# BMS-MCU.net
KiCad netlist of a schematic drawn in Altium Designer
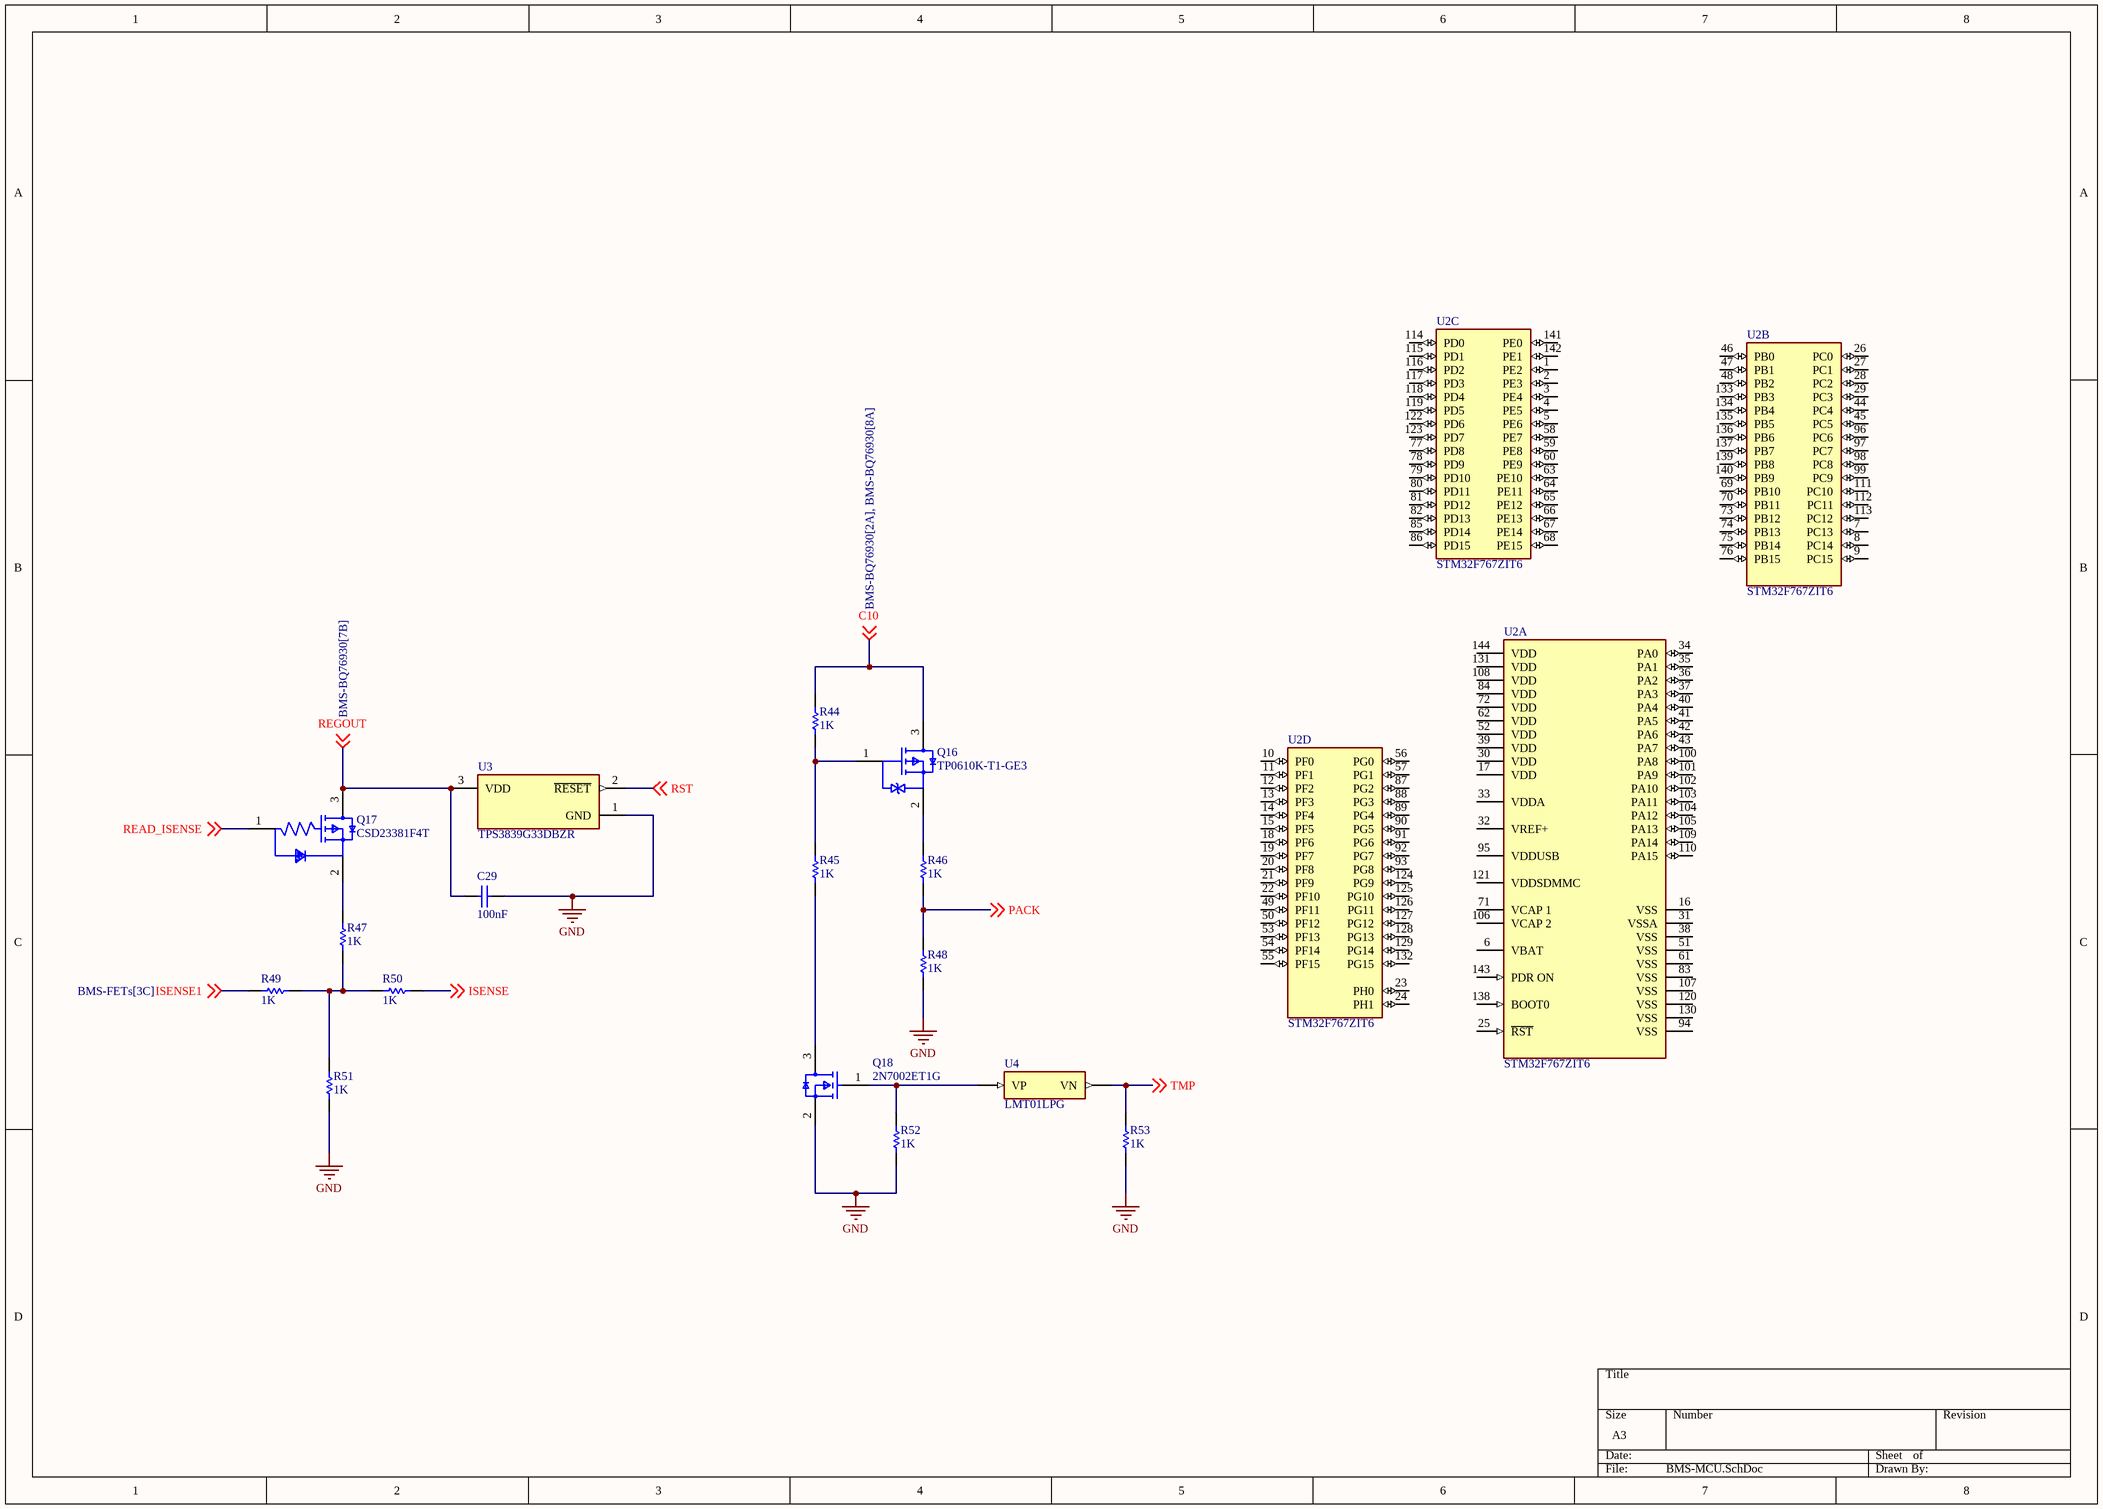
[diagram p0: BMS-MCU.SchDoc]

(export (version "E")
  (design (tool "Eeschema 10.0.6"))
  (components
    (comp (ref "C29")
      (value "885012206046")
      (footprint "WCAP-CSGP_0603_L1.6W0.8H0.8_Reflow")
      (fields (field (name "TOLERANCE") "10%") (field (name "CAPACITANCE") "100nF"))
      (libsource (lib "BMS-lib") (part "CMP-03913-53914755-1"))
    )
    (comp (ref "Q16")
      (value "TP0610K-T1-GE3")
      (footprint "FP-S-03946-IPC_C")
      (description "MOSFET P-CH 60V 185MA SOT23-3")
      (libsource (lib "BMS-lib") (part "CMP-02550-000326-1"))
    )
    (comp (ref "Q17")
      (value "CSD23381F4T")
      (footprint "FP-YJC0003A-MFG")
      (description "MOSFET P-CH 12V 2.3A 3PICOSTAR")
      (libsource (lib "BMS-lib") (part "CMP-04962-000081-1"))
    )
    (comp (ref "Q18")
      (value "2N7002ET1G")
      (footprint "FP-318-08-MFG")
      (description "MOSFET N-CH 60V 260MA SOT-23")
      (libsource (lib "BMS-lib") (part "CMP-1058-00769-2"))
    )
    (comp (ref "R44")
      (value "1K")
      (description "Resistor")
      (libsource (lib "Simulation Generic Components") (part "Resistor"))
    )
    (comp (ref "R45")
      (value "1K")
      (description "Resistor")
      (libsource (lib "Simulation Generic Components") (part "Resistor"))
    )
    (comp (ref "R46")
      (value "1K")
      (description "Resistor")
      (libsource (lib "Simulation Generic Components") (part "Resistor"))
    )
    (comp (ref "R47")
      (value "1K")
      (description "Resistor")
      (libsource (lib "Simulation Generic Components") (part "Resistor"))
    )
    (comp (ref "R48")
      (value "1K")
      (description "Resistor")
      (libsource (lib "Simulation Generic Components") (part "Resistor"))
    )
    (comp (ref "R49")
      (value "1K")
      (description "Resistor")
      (libsource (lib "Simulation Generic Components") (part "Resistor"))
    )
    (comp (ref "R50")
      (value "1K")
      (description "Resistor")
      (libsource (lib "Simulation Generic Components") (part "Resistor"))
    )
    (comp (ref "R51")
      (value "1K")
      (description "Resistor")
      (libsource (lib "Simulation Generic Components") (part "Resistor"))
    )
    (comp (ref "R52")
      (value "1K")
      (description "Resistor")
      (libsource (lib "Simulation Generic Components") (part "Resistor"))
    )
    (comp (ref "R53")
      (value "1K")
      (description "Resistor")
      (libsource (lib "Simulation Generic Components") (part "Resistor"))
    )
    (comp (ref "U2")
      (value "STM32F767ZIT6")
      (footprint "FP-LQFP144-1A-IPC_B")
      (description "IC MCU 32BIT 2MB FLASH 144LQFP")
      (fields
        (field (name "OCTOPART") "https://octopart.com/stm32f767zit6-stmicroelectronics-70527068")
        (field (name "MANUFACTURER") "STMicroelectronics")
      )
      (libsource (lib "BMS-lib") (part "CMP-12105-000074-1"))
    )
    (comp (ref "U3")
      (value "TPS3839G33DBZR")
      (footprint "FP-DBZ0003A-MFG")
      (description "IC SUPERVISOR 1 CHANNEL SOT23-3")
      (libsource (lib "BMS-lib") (part "CMP-04919-000025-1"))
    )
    (comp (ref "U4")
      (value "LMT01LPG")
      (footprint "FP-LPG0002A-MFG")
      (description "SENSOR DIGITAL -50C-150C TO92-2")
      (fields
        (field (name "OCTOPART") "https://octopart.com/lmt01lpg-texas+instruments-60770464")
        (field (name "MANUFACTURER") "Texas Instruments")
      )
      (libsource (lib "BMS-lib") (part "CMP-04948-000023-1"))
    )
  )
  (nets
    (net (code "1") (name "C10") (class "Default")
      (node (ref "Q16") (pin "3") (pinfunction "D_3") (pintype "passive"))
      (node (ref "R44") (pin "2") (pinfunction "2_2") (pintype "passive"))
    )
    (net (code "2") (name "GND") (class "Default")
      (node (ref "C29") (pin "2") (pinfunction "2_2") (pintype "passive"))
      (node (ref "Q18") (pin "2") (pinfunction "Source_2") (pintype "passive"))
      (node (ref "R48") (pin "1") (pinfunction "1_1") (pintype "passive"))
      (node (ref "R51") (pin "1") (pinfunction "1_1") (pintype "passive"))
      (node (ref "R52") (pin "1") (pinfunction "1_1") (pintype "passive"))
      (node (ref "R53") (pin "1") (pinfunction "1_1") (pintype "passive"))
      (node (ref "U3") (pin "1") (pinfunction "GND_1") (pintype "power_in"))
    )
    (net (code "3") (name "ISENSE") (class "Default")
      (node (ref "R50") (pin "1") (pinfunction "1_1") (pintype "passive"))
    )
    (net (code "4") (name "ISENSE1") (class "Default")
      (node (ref "R49") (pin "2") (pinfunction "2_2") (pintype "passive"))
    )
    (net (code "5") (name "Net-(Q16-G)") (class "Default")
      (node (ref "Q16") (pin "1") (pinfunction "G_1") (pintype "passive"))
      (node (ref "R44") (pin "1") (pinfunction "1_1") (pintype "passive"))
      (node (ref "R45") (pin "2") (pinfunction "2_2") (pintype "passive"))
    )
    (net (code "6") (name "Net-(Q16-S)") (class "Default")
      (node (ref "Q16") (pin "2") (pinfunction "S_2") (pintype "passive"))
      (node (ref "R46") (pin "2") (pinfunction "2_2") (pintype "passive"))
    )
    (net (code "7") (name "Net-(Q17-S)") (class "Default")
      (node (ref "Q17") (pin "2") (pinfunction "S_2") (pintype "passive"))
      (node (ref "R47") (pin "2") (pinfunction "2_2") (pintype "passive"))
    )
    (net (code "8") (name "Net-(Q18-Drain)") (class "Default")
      (node (ref "Q18") (pin "3") (pinfunction "Drain_3") (pintype "passive"))
      (node (ref "R45") (pin "1") (pinfunction "1_1") (pintype "passive"))
    )
    (net (code "9") (name "Net-(Q18-Gate)") (class "Default")
      (node (ref "Q18") (pin "1") (pinfunction "Gate_1") (pintype "passive"))
      (node (ref "R52") (pin "2") (pinfunction "2_2") (pintype "passive"))
      (node (ref "U4") (pin "2") (pinfunction "VP_2") (pintype "input"))
    )
    (net (code "10") (name "Net-(R47-Pad1)") (class "Default")
      (node (ref "R47") (pin "1") (pinfunction "1_1") (pintype "passive"))
      (node (ref "R49") (pin "1") (pinfunction "1_1") (pintype "passive"))
      (node (ref "R50") (pin "2") (pinfunction "2_2") (pintype "passive"))
      (node (ref "R51") (pin "2") (pinfunction "2_2") (pintype "passive"))
    )
    (net (code "11") (name "PACK") (class "Default")
      (node (ref "R46") (pin "1") (pinfunction "1_1") (pintype "passive"))
      (node (ref "R48") (pin "2") (pinfunction "2_2") (pintype "passive"))
    )
    (net (code "12") (name "READ_ISENSE") (class "Default")
      (node (ref "Q17") (pin "1") (pinfunction "G_1") (pintype "passive"))
    )
    (net (code "13") (name "REGOUT") (class "Default")
      (node (ref "C29") (pin "1") (pinfunction "1_1") (pintype "passive"))
      (node (ref "Q17") (pin "3") (pinfunction "D_3") (pintype "passive"))
      (node (ref "U3") (pin "3") (pinfunction "VDD_3") (pintype "power_in"))
    )
    (net (code "14") (name "RST") (class "Default")
      (node (ref "U3") (pin "2") (pinfunction "~{RESET}_2") (pintype "output"))
    )
    (net (code "15") (name "TMP") (class "Default")
      (node (ref "R53") (pin "2") (pinfunction "2_2") (pintype "passive"))
      (node (ref "U4") (pin "1") (pinfunction "VN_1") (pintype "output"))
    )
    (net (code "16") (name "unconnected-(U2A-BOOT0-Pad138)") (class "Default")
      (node (ref "U2") (pin "138") (pinfunction "BOOT0_138") (pintype "input"))
    )
    (net (code "17") (name "unconnected-(U2A-PA0-Pad34)") (class "Default")
      (node (ref "U2") (pin "34") (pinfunction "PA0_34") (pintype "bidirectional"))
    )
    (net (code "18") (name "unconnected-(U2A-PA1-Pad35)") (class "Default")
      (node (ref "U2") (pin "35") (pinfunction "PA1_35") (pintype "bidirectional"))
    )
    (net (code "19") (name "unconnected-(U2A-PA2-Pad36)") (class "Default")
      (node (ref "U2") (pin "36") (pinfunction "PA2_36") (pintype "bidirectional"))
    )
    (net (code "20") (name "unconnected-(U2A-PA3-Pad37)") (class "Default")
      (node (ref "U2") (pin "37") (pinfunction "PA3_37") (pintype "bidirectional"))
    )
    (net (code "21") (name "unconnected-(U2A-PA4-Pad40)") (class "Default")
      (node (ref "U2") (pin "40") (pinfunction "PA4_40") (pintype "bidirectional"))
    )
    (net (code "22") (name "unconnected-(U2A-PA5-Pad41)") (class "Default")
      (node (ref "U2") (pin "41") (pinfunction "PA5_41") (pintype "bidirectional"))
    )
    (net (code "23") (name "unconnected-(U2A-PA6-Pad42)") (class "Default")
      (node (ref "U2") (pin "42") (pinfunction "PA6_42") (pintype "bidirectional"))
    )
    (net (code "24") (name "unconnected-(U2A-PA7-Pad43)") (class "Default")
      (node (ref "U2") (pin "43") (pinfunction "PA7_43") (pintype "bidirectional"))
    )
    (net (code "25") (name "unconnected-(U2A-PA8-Pad100)") (class "Default")
      (node (ref "U2") (pin "100") (pinfunction "PA8_100") (pintype "bidirectional"))
    )
    (net (code "26") (name "unconnected-(U2A-PA9-Pad101)") (class "Default")
      (node (ref "U2") (pin "101") (pinfunction "PA9_101") (pintype "bidirectional"))
    )
    (net (code "27") (name "unconnected-(U2A-PA10-Pad102)") (class "Default")
      (node (ref "U2") (pin "102") (pinfunction "PA10_102") (pintype "bidirectional"))
    )
    (net (code "28") (name "unconnected-(U2A-PA11-Pad103)") (class "Default")
      (node (ref "U2") (pin "103") (pinfunction "PA11_103") (pintype "bidirectional"))
    )
    (net (code "29") (name "unconnected-(U2A-PA12-Pad104)") (class "Default")
      (node (ref "U2") (pin "104") (pinfunction "PA12_104") (pintype "bidirectional"))
    )
    (net (code "30") (name "unconnected-(U2A-PA13-Pad105)") (class "Default")
      (node (ref "U2") (pin "105") (pinfunction "PA13_105") (pintype "bidirectional"))
    )
    (net (code "31") (name "unconnected-(U2A-PA14-Pad109)") (class "Default")
      (node (ref "U2") (pin "109") (pinfunction "PA14_109") (pintype "bidirectional"))
    )
    (net (code "32") (name "unconnected-(U2A-PA15-Pad110)") (class "Default")
      (node (ref "U2") (pin "110") (pinfunction "PA15_110") (pintype "bidirectional"))
    )
    (net (code "33") (name "unconnected-(U2A-PDR_ON-Pad143)") (class "Default")
      (node (ref "U2") (pin "143") (pinfunction "PDR_ON_143") (pintype "input"))
    )
    (net (code "34") (name "unconnected-(U2A-VBAT-Pad6)") (class "Default")
      (node (ref "U2") (pin "6") (pinfunction "VBAT_6") (pintype "power_in"))
    )
    (net (code "35") (name "unconnected-(U2A-VCAP_1-Pad71)") (class "Default")
      (node (ref "U2") (pin "71") (pinfunction "VCAP_1_71") (pintype "power_in"))
    )
    (net (code "36") (name "unconnected-(U2A-VCAP_2-Pad106)") (class "Default")
      (node (ref "U2") (pin "106") (pinfunction "VCAP_2_106") (pintype "power_in"))
    )
    (net (code "37") (name "unconnected-(U2A-VDD-Pad17)") (class "Default")
      (node (ref "U2") (pin "17") (pinfunction "VDD_17") (pintype "power_in"))
    )
    (net (code "38") (name "unconnected-(U2A-VDD-Pad30)") (class "Default")
      (node (ref "U2") (pin "30") (pinfunction "VDD_30") (pintype "power_in"))
    )
    (net (code "39") (name "unconnected-(U2A-VDD-Pad39)") (class "Default")
      (node (ref "U2") (pin "39") (pinfunction "VDD_39") (pintype "power_in"))
    )
    (net (code "40") (name "unconnected-(U2A-VDD-Pad52)") (class "Default")
      (node (ref "U2") (pin "52") (pinfunction "VDD_52") (pintype "power_in"))
    )
    (net (code "41") (name "unconnected-(U2A-VDD-Pad62)") (class "Default")
      (node (ref "U2") (pin "62") (pinfunction "VDD_62") (pintype "power_in"))
    )
    (net (code "42") (name "unconnected-(U2A-VDD-Pad72)") (class "Default")
      (node (ref "U2") (pin "72") (pinfunction "VDD_72") (pintype "power_in"))
    )
    (net (code "43") (name "unconnected-(U2A-VDD-Pad84)") (class "Default")
      (node (ref "U2") (pin "84") (pinfunction "VDD_84") (pintype "power_in"))
    )
    (net (code "44") (name "unconnected-(U2A-VDD-Pad108)") (class "Default")
      (node (ref "U2") (pin "108") (pinfunction "VDD_108") (pintype "power_in"))
    )
    (net (code "45") (name "unconnected-(U2A-VDD-Pad131)") (class "Default")
      (node (ref "U2") (pin "131") (pinfunction "VDD_131") (pintype "power_in"))
    )
    (net (code "46") (name "unconnected-(U2A-VDD-Pad144)") (class "Default")
      (node (ref "U2") (pin "144") (pinfunction "VDD_144") (pintype "power_in"))
    )
    (net (code "47") (name "unconnected-(U2A-VDDA-Pad33)") (class "Default")
      (node (ref "U2") (pin "33") (pinfunction "VDDA_33") (pintype "power_in"))
    )
    (net (code "48") (name "unconnected-(U2A-VDDSDMMC-Pad121)") (class "Default")
      (node (ref "U2") (pin "121") (pinfunction "VDDSDMMC_121") (pintype "power_in"))
    )
    (net (code "49") (name "unconnected-(U2A-VDDUSB-Pad95)") (class "Default")
      (node (ref "U2") (pin "95") (pinfunction "VDDUSB_95") (pintype "power_in"))
    )
    (net (code "50") (name "unconnected-(U2A-VREF+-Pad32)") (class "Default")
      (node (ref "U2") (pin "32") (pinfunction "VREF+_32") (pintype "power_in"))
    )
    (net (code "51") (name "unconnected-(U2A-VSS-Pad16)") (class "Default")
      (node (ref "U2") (pin "16") (pinfunction "VSS_16") (pintype "power_in"))
    )
    (net (code "52") (name "unconnected-(U2A-VSS-Pad38)") (class "Default")
      (node (ref "U2") (pin "38") (pinfunction "VSS_38") (pintype "power_in"))
    )
    (net (code "53") (name "unconnected-(U2A-VSS-Pad51)") (class "Default")
      (node (ref "U2") (pin "51") (pinfunction "VSS_51") (pintype "power_in"))
    )
    (net (code "54") (name "unconnected-(U2A-VSS-Pad61)") (class "Default")
      (node (ref "U2") (pin "61") (pinfunction "VSS_61") (pintype "power_in"))
    )
    (net (code "55") (name "unconnected-(U2A-VSS-Pad83)") (class "Default")
      (node (ref "U2") (pin "83") (pinfunction "VSS_83") (pintype "power_in"))
    )
    (net (code "56") (name "unconnected-(U2A-VSS-Pad94)") (class "Default")
      (node (ref "U2") (pin "94") (pinfunction "VSS_94") (pintype "power_in"))
    )
    (net (code "57") (name "unconnected-(U2A-VSS-Pad107)") (class "Default")
      (node (ref "U2") (pin "107") (pinfunction "VSS_107") (pintype "power_in"))
    )
    (net (code "58") (name "unconnected-(U2A-VSS-Pad120)") (class "Default")
      (node (ref "U2") (pin "120") (pinfunction "VSS_120") (pintype "power_in"))
    )
    (net (code "59") (name "unconnected-(U2A-VSS-Pad130)") (class "Default")
      (node (ref "U2") (pin "130") (pinfunction "VSS_130") (pintype "power_in"))
    )
    (net (code "60") (name "unconnected-(U2A-VSSA-Pad31)") (class "Default")
      (node (ref "U2") (pin "31") (pinfunction "VSSA_31") (pintype "power_in"))
    )
    (net (code "61") (name "unconnected-(U2A-~{RST}-Pad25)") (class "Default")
      (node (ref "U2") (pin "25") (pinfunction "~{RST}_25") (pintype "input"))
    )
    (net (code "62") (name "unconnected-(U2B-PB0-Pad46)") (class "Default")
      (node (ref "U2") (pin "46") (pinfunction "PB0_46") (pintype "bidirectional"))
    )
    (net (code "63") (name "unconnected-(U2B-PB1-Pad47)") (class "Default")
      (node (ref "U2") (pin "47") (pinfunction "PB1_47") (pintype "bidirectional"))
    )
    (net (code "64") (name "unconnected-(U2B-PB2-Pad48)") (class "Default")
      (node (ref "U2") (pin "48") (pinfunction "PB2_48") (pintype "bidirectional"))
    )
    (net (code "65") (name "unconnected-(U2B-PB3-Pad133)") (class "Default")
      (node (ref "U2") (pin "133") (pinfunction "PB3_133") (pintype "bidirectional"))
    )
    (net (code "66") (name "unconnected-(U2B-PB4-Pad134)") (class "Default")
      (node (ref "U2") (pin "134") (pinfunction "PB4_134") (pintype "bidirectional"))
    )
    (net (code "67") (name "unconnected-(U2B-PB5-Pad135)") (class "Default")
      (node (ref "U2") (pin "135") (pinfunction "PB5_135") (pintype "bidirectional"))
    )
    (net (code "68") (name "unconnected-(U2B-PB6-Pad136)") (class "Default")
      (node (ref "U2") (pin "136") (pinfunction "PB6_136") (pintype "bidirectional"))
    )
    (net (code "69") (name "unconnected-(U2B-PB7-Pad137)") (class "Default")
      (node (ref "U2") (pin "137") (pinfunction "PB7_137") (pintype "bidirectional"))
    )
    (net (code "70") (name "unconnected-(U2B-PB8-Pad139)") (class "Default")
      (node (ref "U2") (pin "139") (pinfunction "PB8_139") (pintype "bidirectional"))
    )
    (net (code "71") (name "unconnected-(U2B-PB9-Pad140)") (class "Default")
      (node (ref "U2") (pin "140") (pinfunction "PB9_140") (pintype "bidirectional"))
    )
    (net (code "72") (name "unconnected-(U2B-PB10-Pad69)") (class "Default")
      (node (ref "U2") (pin "69") (pinfunction "PB10_69") (pintype "bidirectional"))
    )
    (net (code "73") (name "unconnected-(U2B-PB11-Pad70)") (class "Default")
      (node (ref "U2") (pin "70") (pinfunction "PB11_70") (pintype "bidirectional"))
    )
    (net (code "74") (name "unconnected-(U2B-PB12-Pad73)") (class "Default")
      (node (ref "U2") (pin "73") (pinfunction "PB12_73") (pintype "bidirectional"))
    )
    (net (code "75") (name "unconnected-(U2B-PB13-Pad74)") (class "Default")
      (node (ref "U2") (pin "74") (pinfunction "PB13_74") (pintype "bidirectional"))
    )
    (net (code "76") (name "unconnected-(U2B-PB14-Pad75)") (class "Default")
      (node (ref "U2") (pin "75") (pinfunction "PB14_75") (pintype "bidirectional"))
    )
    (net (code "77") (name "unconnected-(U2B-PB15-Pad76)") (class "Default")
      (node (ref "U2") (pin "76") (pinfunction "PB15_76") (pintype "bidirectional"))
    )
    (net (code "78") (name "unconnected-(U2B-PC0-Pad26)") (class "Default")
      (node (ref "U2") (pin "26") (pinfunction "PC0_26") (pintype "bidirectional"))
    )
    (net (code "79") (name "unconnected-(U2B-PC1-Pad27)") (class "Default")
      (node (ref "U2") (pin "27") (pinfunction "PC1_27") (pintype "bidirectional"))
    )
    (net (code "80") (name "unconnected-(U2B-PC2-Pad28)") (class "Default")
      (node (ref "U2") (pin "28") (pinfunction "PC2_28") (pintype "bidirectional"))
    )
    (net (code "81") (name "unconnected-(U2B-PC3-Pad29)") (class "Default")
      (node (ref "U2") (pin "29") (pinfunction "PC3_29") (pintype "bidirectional"))
    )
    (net (code "82") (name "unconnected-(U2B-PC4-Pad44)") (class "Default")
      (node (ref "U2") (pin "44") (pinfunction "PC4_44") (pintype "bidirectional"))
    )
    (net (code "83") (name "unconnected-(U2B-PC5-Pad45)") (class "Default")
      (node (ref "U2") (pin "45") (pinfunction "PC5_45") (pintype "bidirectional"))
    )
    (net (code "84") (name "unconnected-(U2B-PC6-Pad96)") (class "Default")
      (node (ref "U2") (pin "96") (pinfunction "PC6_96") (pintype "bidirectional"))
    )
    (net (code "85") (name "unconnected-(U2B-PC7-Pad97)") (class "Default")
      (node (ref "U2") (pin "97") (pinfunction "PC7_97") (pintype "bidirectional"))
    )
    (net (code "86") (name "unconnected-(U2B-PC8-Pad98)") (class "Default")
      (node (ref "U2") (pin "98") (pinfunction "PC8_98") (pintype "bidirectional"))
    )
    (net (code "87") (name "unconnected-(U2B-PC9-Pad99)") (class "Default")
      (node (ref "U2") (pin "99") (pinfunction "PC9_99") (pintype "bidirectional"))
    )
    (net (code "88") (name "unconnected-(U2B-PC10-Pad111)") (class "Default")
      (node (ref "U2") (pin "111") (pinfunction "PC10_111") (pintype "bidirectional"))
    )
    (net (code "89") (name "unconnected-(U2B-PC11-Pad112)") (class "Default")
      (node (ref "U2") (pin "112") (pinfunction "PC11_112") (pintype "bidirectional"))
    )
    (net (code "90") (name "unconnected-(U2B-PC12-Pad113)") (class "Default")
      (node (ref "U2") (pin "113") (pinfunction "PC12_113") (pintype "bidirectional"))
    )
    (net (code "91") (name "unconnected-(U2B-PC13-Pad7)") (class "Default")
      (node (ref "U2") (pin "7") (pinfunction "PC13_7") (pintype "bidirectional"))
    )
    (net (code "92") (name "unconnected-(U2B-PC14-Pad8)") (class "Default")
      (node (ref "U2") (pin "8") (pinfunction "PC14_8") (pintype "bidirectional"))
    )
    (net (code "93") (name "unconnected-(U2B-PC15-Pad9)") (class "Default")
      (node (ref "U2") (pin "9") (pinfunction "PC15_9") (pintype "bidirectional"))
    )
    (net (code "94") (name "unconnected-(U2C-PD0-Pad114)") (class "Default")
      (node (ref "U2") (pin "114") (pinfunction "PD0_114") (pintype "bidirectional"))
    )
    (net (code "95") (name "unconnected-(U2C-PD1-Pad115)") (class "Default")
      (node (ref "U2") (pin "115") (pinfunction "PD1_115") (pintype "bidirectional"))
    )
    (net (code "96") (name "unconnected-(U2C-PD2-Pad116)") (class "Default")
      (node (ref "U2") (pin "116") (pinfunction "PD2_116") (pintype "bidirectional"))
    )
    (net (code "97") (name "unconnected-(U2C-PD3-Pad117)") (class "Default")
      (node (ref "U2") (pin "117") (pinfunction "PD3_117") (pintype "bidirectional"))
    )
    (net (code "98") (name "unconnected-(U2C-PD4-Pad118)") (class "Default")
      (node (ref "U2") (pin "118") (pinfunction "PD4_118") (pintype "bidirectional"))
    )
    (net (code "99") (name "unconnected-(U2C-PD5-Pad119)") (class "Default")
      (node (ref "U2") (pin "119") (pinfunction "PD5_119") (pintype "bidirectional"))
    )
    (net (code "100") (name "unconnected-(U2C-PD6-Pad122)") (class "Default")
      (node (ref "U2") (pin "122") (pinfunction "PD6_122") (pintype "bidirectional"))
    )
    (net (code "101") (name "unconnected-(U2C-PD7-Pad123)") (class "Default")
      (node (ref "U2") (pin "123") (pinfunction "PD7_123") (pintype "bidirectional"))
    )
    (net (code "102") (name "unconnected-(U2C-PD8-Pad77)") (class "Default")
      (node (ref "U2") (pin "77") (pinfunction "PD8_77") (pintype "bidirectional"))
    )
    (net (code "103") (name "unconnected-(U2C-PD9-Pad78)") (class "Default")
      (node (ref "U2") (pin "78") (pinfunction "PD9_78") (pintype "bidirectional"))
    )
    (net (code "104") (name "unconnected-(U2C-PD10-Pad79)") (class "Default")
      (node (ref "U2") (pin "79") (pinfunction "PD10_79") (pintype "bidirectional"))
    )
    (net (code "105") (name "unconnected-(U2C-PD11-Pad80)") (class "Default")
      (node (ref "U2") (pin "80") (pinfunction "PD11_80") (pintype "bidirectional"))
    )
    (net (code "106") (name "unconnected-(U2C-PD12-Pad81)") (class "Default")
      (node (ref "U2") (pin "81") (pinfunction "PD12_81") (pintype "bidirectional"))
    )
    (net (code "107") (name "unconnected-(U2C-PD13-Pad82)") (class "Default")
      (node (ref "U2") (pin "82") (pinfunction "PD13_82") (pintype "bidirectional"))
    )
    (net (code "108") (name "unconnected-(U2C-PD14-Pad85)") (class "Default")
      (node (ref "U2") (pin "85") (pinfunction "PD14_85") (pintype "bidirectional"))
    )
    (net (code "109") (name "unconnected-(U2C-PD15-Pad86)") (class "Default")
      (node (ref "U2") (pin "86") (pinfunction "PD15_86") (pintype "bidirectional"))
    )
    (net (code "110") (name "unconnected-(U2C-PE0-Pad141)") (class "Default")
      (node (ref "U2") (pin "141") (pinfunction "PE0_141") (pintype "bidirectional"))
    )
    (net (code "111") (name "unconnected-(U2C-PE1-Pad142)") (class "Default")
      (node (ref "U2") (pin "142") (pinfunction "PE1_142") (pintype "bidirectional"))
    )
    (net (code "112") (name "unconnected-(U2C-PE2-Pad1)") (class "Default")
      (node (ref "U2") (pin "1") (pinfunction "PE2_1") (pintype "bidirectional"))
    )
    (net (code "113") (name "unconnected-(U2C-PE3-Pad2)") (class "Default")
      (node (ref "U2") (pin "2") (pinfunction "PE3_2") (pintype "bidirectional"))
    )
    (net (code "114") (name "unconnected-(U2C-PE4-Pad3)") (class "Default")
      (node (ref "U2") (pin "3") (pinfunction "PE4_3") (pintype "bidirectional"))
    )
    (net (code "115") (name "unconnected-(U2C-PE5-Pad4)") (class "Default")
      (node (ref "U2") (pin "4") (pinfunction "PE5_4") (pintype "bidirectional"))
    )
    (net (code "116") (name "unconnected-(U2C-PE6-Pad5)") (class "Default")
      (node (ref "U2") (pin "5") (pinfunction "PE6_5") (pintype "bidirectional"))
    )
    (net (code "117") (name "unconnected-(U2C-PE7-Pad58)") (class "Default")
      (node (ref "U2") (pin "58") (pinfunction "PE7_58") (pintype "bidirectional"))
    )
    (net (code "118") (name "unconnected-(U2C-PE8-Pad59)") (class "Default")
      (node (ref "U2") (pin "59") (pinfunction "PE8_59") (pintype "bidirectional"))
    )
    (net (code "119") (name "unconnected-(U2C-PE9-Pad60)") (class "Default")
      (node (ref "U2") (pin "60") (pinfunction "PE9_60") (pintype "bidirectional"))
    )
    (net (code "120") (name "unconnected-(U2C-PE10-Pad63)") (class "Default")
      (node (ref "U2") (pin "63") (pinfunction "PE10_63") (pintype "bidirectional"))
    )
    (net (code "121") (name "unconnected-(U2C-PE11-Pad64)") (class "Default")
      (node (ref "U2") (pin "64") (pinfunction "PE11_64") (pintype "bidirectional"))
    )
    (net (code "122") (name "unconnected-(U2C-PE12-Pad65)") (class "Default")
      (node (ref "U2") (pin "65") (pinfunction "PE12_65") (pintype "bidirectional"))
    )
    (net (code "123") (name "unconnected-(U2C-PE13-Pad66)") (class "Default")
      (node (ref "U2") (pin "66") (pinfunction "PE13_66") (pintype "bidirectional"))
    )
    (net (code "124") (name "unconnected-(U2C-PE14-Pad67)") (class "Default")
      (node (ref "U2") (pin "67") (pinfunction "PE14_67") (pintype "bidirectional"))
    )
    (net (code "125") (name "unconnected-(U2C-PE15-Pad68)") (class "Default")
      (node (ref "U2") (pin "68") (pinfunction "PE15_68") (pintype "bidirectional"))
    )
    (net (code "126") (name "unconnected-(U2D-PF0-Pad10)") (class "Default")
      (node (ref "U2") (pin "10") (pinfunction "PF0_10") (pintype "bidirectional"))
    )
    (net (code "127") (name "unconnected-(U2D-PF1-Pad11)") (class "Default")
      (node (ref "U2") (pin "11") (pinfunction "PF1_11") (pintype "bidirectional"))
    )
    (net (code "128") (name "unconnected-(U2D-PF2-Pad12)") (class "Default")
      (node (ref "U2") (pin "12") (pinfunction "PF2_12") (pintype "bidirectional"))
    )
    (net (code "129") (name "unconnected-(U2D-PF3-Pad13)") (class "Default")
      (node (ref "U2") (pin "13") (pinfunction "PF3_13") (pintype "bidirectional"))
    )
    (net (code "130") (name "unconnected-(U2D-PF4-Pad14)") (class "Default")
      (node (ref "U2") (pin "14") (pinfunction "PF4_14") (pintype "bidirectional"))
    )
    (net (code "131") (name "unconnected-(U2D-PF5-Pad15)") (class "Default")
      (node (ref "U2") (pin "15") (pinfunction "PF5_15") (pintype "bidirectional"))
    )
    (net (code "132") (name "unconnected-(U2D-PF6-Pad18)") (class "Default")
      (node (ref "U2") (pin "18") (pinfunction "PF6_18") (pintype "bidirectional"))
    )
    (net (code "133") (name "unconnected-(U2D-PF7-Pad19)") (class "Default")
      (node (ref "U2") (pin "19") (pinfunction "PF7_19") (pintype "bidirectional"))
    )
    (net (code "134") (name "unconnected-(U2D-PF8-Pad20)") (class "Default")
      (node (ref "U2") (pin "20") (pinfunction "PF8_20") (pintype "bidirectional"))
    )
    (net (code "135") (name "unconnected-(U2D-PF9-Pad21)") (class "Default")
      (node (ref "U2") (pin "21") (pinfunction "PF9_21") (pintype "bidirectional"))
    )
    (net (code "136") (name "unconnected-(U2D-PF10-Pad22)") (class "Default")
      (node (ref "U2") (pin "22") (pinfunction "PF10_22") (pintype "bidirectional"))
    )
    (net (code "137") (name "unconnected-(U2D-PF11-Pad49)") (class "Default")
      (node (ref "U2") (pin "49") (pinfunction "PF11_49") (pintype "bidirectional"))
    )
    (net (code "138") (name "unconnected-(U2D-PF12-Pad50)") (class "Default")
      (node (ref "U2") (pin "50") (pinfunction "PF12_50") (pintype "bidirectional"))
    )
    (net (code "139") (name "unconnected-(U2D-PF13-Pad53)") (class "Default")
      (node (ref "U2") (pin "53") (pinfunction "PF13_53") (pintype "bidirectional"))
    )
    (net (code "140") (name "unconnected-(U2D-PF14-Pad54)") (class "Default")
      (node (ref "U2") (pin "54") (pinfunction "PF14_54") (pintype "bidirectional"))
    )
    (net (code "141") (name "unconnected-(U2D-PF15-Pad55)") (class "Default")
      (node (ref "U2") (pin "55") (pinfunction "PF15_55") (pintype "bidirectional"))
    )
    (net (code "142") (name "unconnected-(U2D-PG0-Pad56)") (class "Default")
      (node (ref "U2") (pin "56") (pinfunction "PG0_56") (pintype "bidirectional"))
    )
    (net (code "143") (name "unconnected-(U2D-PG1-Pad57)") (class "Default")
      (node (ref "U2") (pin "57") (pinfunction "PG1_57") (pintype "bidirectional"))
    )
    (net (code "144") (name "unconnected-(U2D-PG2-Pad87)") (class "Default")
      (node (ref "U2") (pin "87") (pinfunction "PG2_87") (pintype "bidirectional"))
    )
    (net (code "145") (name "unconnected-(U2D-PG3-Pad88)") (class "Default")
      (node (ref "U2") (pin "88") (pinfunction "PG3_88") (pintype "bidirectional"))
    )
    (net (code "146") (name "unconnected-(U2D-PG4-Pad89)") (class "Default")
      (node (ref "U2") (pin "89") (pinfunction "PG4_89") (pintype "bidirectional"))
    )
    (net (code "147") (name "unconnected-(U2D-PG5-Pad90)") (class "Default")
      (node (ref "U2") (pin "90") (pinfunction "PG5_90") (pintype "bidirectional"))
    )
    (net (code "148") (name "unconnected-(U2D-PG6-Pad91)") (class "Default")
      (node (ref "U2") (pin "91") (pinfunction "PG6_91") (pintype "bidirectional"))
    )
    (net (code "149") (name "unconnected-(U2D-PG7-Pad92)") (class "Default")
      (node (ref "U2") (pin "92") (pinfunction "PG7_92") (pintype "bidirectional"))
    )
    (net (code "150") (name "unconnected-(U2D-PG8-Pad93)") (class "Default")
      (node (ref "U2") (pin "93") (pinfunction "PG8_93") (pintype "bidirectional"))
    )
    (net (code "151") (name "unconnected-(U2D-PG9-Pad124)") (class "Default")
      (node (ref "U2") (pin "124") (pinfunction "PG9_124") (pintype "bidirectional"))
    )
    (net (code "152") (name "unconnected-(U2D-PG10-Pad125)") (class "Default")
      (node (ref "U2") (pin "125") (pinfunction "PG10_125") (pintype "bidirectional"))
    )
    (net (code "153") (name "unconnected-(U2D-PG11-Pad126)") (class "Default")
      (node (ref "U2") (pin "126") (pinfunction "PG11_126") (pintype "bidirectional"))
    )
    (net (code "154") (name "unconnected-(U2D-PG12-Pad127)") (class "Default")
      (node (ref "U2") (pin "127") (pinfunction "PG12_127") (pintype "bidirectional"))
    )
    (net (code "155") (name "unconnected-(U2D-PG13-Pad128)") (class "Default")
      (node (ref "U2") (pin "128") (pinfunction "PG13_128") (pintype "bidirectional"))
    )
    (net (code "156") (name "unconnected-(U2D-PG14-Pad129)") (class "Default")
      (node (ref "U2") (pin "129") (pinfunction "PG14_129") (pintype "bidirectional"))
    )
    (net (code "157") (name "unconnected-(U2D-PG15-Pad132)") (class "Default")
      (node (ref "U2") (pin "132") (pinfunction "PG15_132") (pintype "bidirectional"))
    )
    (net (code "158") (name "unconnected-(U2D-PH0-Pad23)") (class "Default")
      (node (ref "U2") (pin "23") (pinfunction "PH0_23") (pintype "bidirectional"))
    )
    (net (code "159") (name "unconnected-(U2D-PH1-Pad24)") (class "Default")
      (node (ref "U2") (pin "24") (pinfunction "PH1_24") (pintype "bidirectional"))
    )
  )
)
